# CopterControl_Mag_Pressure.net
KiCad netlist of a schematic drawn in Altium Designer
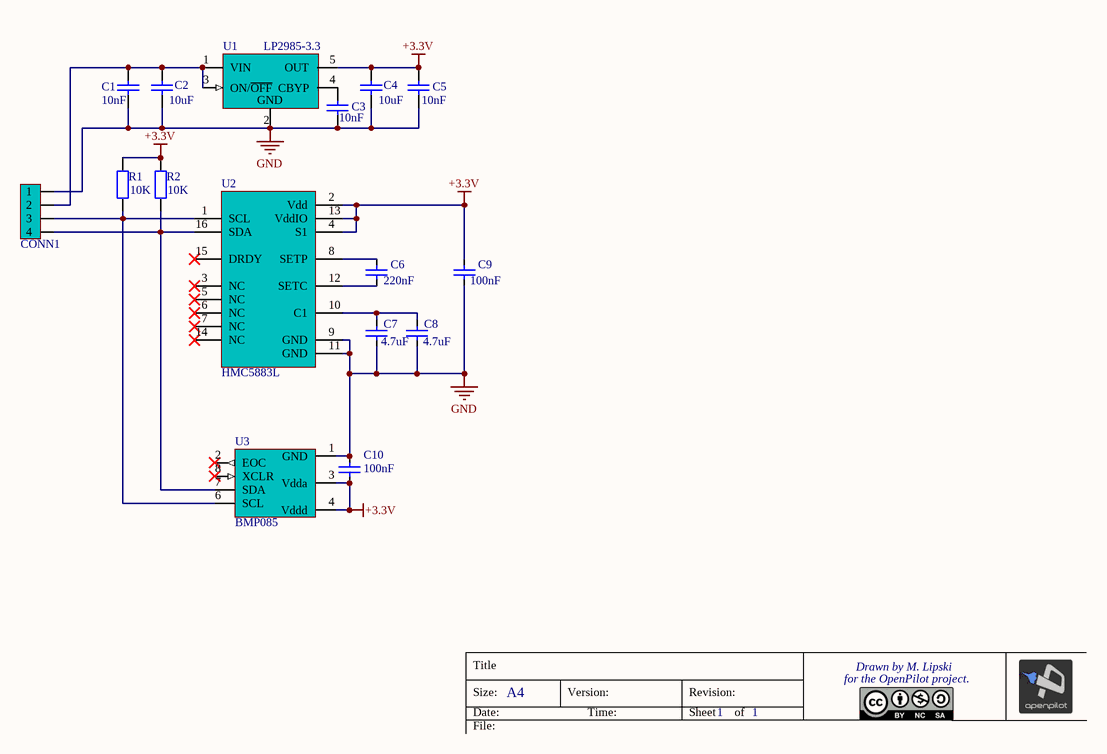
[diagram p0: CopterControl Mag & Pressure.SchDoc]

(export (version "E")
  (design (tool "Eeschema 10.0.6"))
  (components
    (comp (ref "C1")
      (value "10nF")
      (footprint "CAP603L")
      (description "Capacitor SMD")
      (fields (field (name "Comment") "Cap603") (field (name "PUBLISHER") "The OpenPilot Project"))
      (libsource (lib "OpenPilot") (part "Cap603"))
    )
    (comp (ref "C2")
      (value "10uF")
      (footprint "CAP805L")
      (description "Capacitor SMD")
      (fields (field (name "Comment") "Cap805") (field (name "PUBLISHER") "The OpenPilot Project"))
      (libsource (lib "OpenPilot") (part "Cap805"))
    )
    (comp (ref "C3")
      (value "10nF")
      (footprint "CAP603L")
      (description "Capacitor SMD")
      (fields (field (name "Comment") "Cap603") (field (name "PUBLISHER") "The OpenPilot Project"))
      (libsource (lib "OpenPilot") (part "Cap603"))
    )
    (comp (ref "C4")
      (value "10uF")
      (footprint "CAP805L")
      (description "Capacitor SMD")
      (fields (field (name "Comment") "Cap805") (field (name "PUBLISHER") "The OpenPilot Project"))
      (libsource (lib "OpenPilot") (part "Cap805"))
    )
    (comp (ref "C5")
      (value "10nF")
      (footprint "CAP603L")
      (description "Capacitor SMD")
      (fields (field (name "Comment") "Cap603") (field (name "PUBLISHER") "The OpenPilot Project"))
      (libsource (lib "OpenPilot") (part "Cap603"))
    )
    (comp (ref "C6")
      (value "220nF")
      (footprint "CAP603L")
      (description "Capacitor SMD")
      (fields (field (name "Comment") "Cap603") (field (name "PUBLISHER") "The OpenPilot Project"))
      (libsource (lib "") (part "Cap603_1"))
    )
    (comp (ref "C7")
      (value "4.7uF")
      (footprint "CAP603L")
      (description "Capacitor SMD")
      (fields (field (name "Comment") "Cap603") (field (name "PUBLISHER") "The OpenPilot Project"))
      (libsource (lib "") (part "Cap603_1"))
    )
    (comp (ref "C8")
      (value "4.7uF")
      (footprint "CAP603L")
      (description "Capacitor SMD")
      (fields (field (name "Comment") "Cap603") (field (name "PUBLISHER") "The OpenPilot Project"))
      (libsource (lib "") (part "Cap603_1"))
    )
    (comp (ref "C9")
      (value "100nF")
      (footprint "CAP603L")
      (description "Capacitor SMD")
      (fields (field (name "Comment") "Cap603") (field (name "PUBLISHER") "The OpenPilot Project"))
      (libsource (lib "") (part "Cap603_1"))
    )
    (comp (ref "C10")
      (value "100nF")
      (footprint "CAP603L")
      (description "Capacitor SMD")
      (fields (field (name "Comment") "Cap603") (field (name "PUBLISHER") "The OpenPilot Project"))
      (libsource (lib "") (part "Cap603_1"))
    )
    (comp (ref "CONN1")
      (value "JST-SH 4-pin Side Entry Socket")
      (footprint "JST SH 4 Pin Side Entry")
      (fields
        (field (name "MANUFACTURER") "Generic Components")
        (field (name "PUBLISHER") "The OpenPilot Project")
      )
      (libsource (lib "OpenPilot") (part "JST-SH 4-pin Side Entry Socket"))
    )
    (comp (ref "R1")
      (value "10K")
      (footprint "RES603N")
      (description "Resistor SMD")
      (fields (field (name "Comment") "Res603") (field (name "PUBLISHER") "The OpenPilot Project"))
      (libsource (lib "OpenPilot") (part "Res603"))
    )
    (comp (ref "R2")
      (value "10K")
      (footprint "RES603N")
      (description "Resistor SMD")
      (fields (field (name "Comment") "Res603") (field (name "PUBLISHER") "The OpenPilot Project"))
      (libsource (lib "OpenPilot") (part "Res603"))
    )
    (comp (ref "U1")
      (value "LP2985-3.3")
      (footprint "SOT23-5L")
      (description "3.3V 150mA LDO Regulator")
      (libsource (lib "OpenPilot") (part "LP2985-3.3"))
    )
    (comp (ref "U2")
      (value "HMC5883L")
      (footprint "LPCC-16")
      (description "IC, Magnetometer, 3 axis, +/- 8 Oe, I2C, 160Hz")
      (fields (field (name "MANUFACTURER") "Honeywell") (field (name "PUBLISHER") "The OpenPilot Project"))
      (libsource (lib "OpenPilot") (part "HMC5883L"))
    )
    (comp (ref "U3")
      (value "BMP085")
      (footprint "BMP085")
      (description "Barometric Pressure Sensor")
      (libsource (lib "OpenPilot") (part "BMP085"))
    )
  )
  (nets
    (net (code "1") (name "+3.3V") (class "Default")
      (node (ref "C10") (pin "1") (pinfunction "1_1") (pintype "passive"))
      (node (ref "C4") (pin "1") (pinfunction "1_1") (pintype "passive"))
      (node (ref "C5") (pin "1") (pinfunction "1_1") (pintype "passive"))
      (node (ref "C9") (pin "1") (pinfunction "1_1") (pintype "passive"))
      (node (ref "R1") (pin "2") (pinfunction "2_2") (pintype "passive"))
      (node (ref "R2") (pin "2") (pinfunction "2_2") (pintype "passive"))
      (node (ref "U1") (pin "5") (pinfunction "OUT_5") (pintype "power_in"))
      (node (ref "U2") (pin "13") (pinfunction "VddIO_13") (pintype "passive"))
      (node (ref "U2") (pin "2") (pinfunction "Vdd_2") (pintype "power_in"))
      (node (ref "U2") (pin "4") (pinfunction "S1_4") (pintype "passive"))
      (node (ref "U3") (pin "3") (pinfunction "Vdda_3") (pintype "power_in"))
      (node (ref "U3") (pin "4") (pinfunction "Vddd_4") (pintype "power_in"))
    )
    (net (code "2") (name "GND") (class "Default")
      (node (ref "C1") (pin "2") (pinfunction "2_2") (pintype "passive"))
      (node (ref "C10") (pin "2") (pinfunction "2_2") (pintype "passive"))
      (node (ref "C2") (pin "2") (pinfunction "2_2") (pintype "passive"))
      (node (ref "C3") (pin "2") (pinfunction "2_2") (pintype "passive"))
      (node (ref "C4") (pin "2") (pinfunction "2_2") (pintype "passive"))
      (node (ref "C5") (pin "2") (pinfunction "2_2") (pintype "passive"))
      (node (ref "C7") (pin "2") (pinfunction "2_2") (pintype "passive"))
      (node (ref "C8") (pin "2") (pinfunction "2_2") (pintype "passive"))
      (node (ref "C9") (pin "2") (pinfunction "2_2") (pintype "passive"))
      (node (ref "CONN1") (pin "1") (pinfunction "1_1") (pintype "passive"))
      (node (ref "U1") (pin "2") (pinfunction "GND_2") (pintype "power_in"))
      (node (ref "U2") (pin "11") (pinfunction "GND_11") (pintype "passive"))
      (node (ref "U2") (pin "9") (pinfunction "GND_9") (pintype "passive"))
      (node (ref "U3") (pin "1") (pinfunction "GND_1") (pintype "power_in"))
    )
    (net (code "3") (name "Net-(U1-CBYP)") (class "Default")
      (node (ref "C3") (pin "1") (pinfunction "1_1") (pintype "passive"))
      (node (ref "U1") (pin "4") (pinfunction "CBYP_4") (pintype "passive"))
    )
    (net (code "4") (name "Net-(U1-ON{slash}~{OFF})") (class "Default")
      (node (ref "C1") (pin "1") (pinfunction "1_1") (pintype "passive"))
      (node (ref "C2") (pin "1") (pinfunction "1_1") (pintype "passive"))
      (node (ref "CONN1") (pin "2") (pinfunction "2_2") (pintype "passive"))
      (node (ref "U1") (pin "1") (pinfunction "VIN_1") (pintype "power_in"))
      (node (ref "U1") (pin "3") (pinfunction "ON/~{OFF}_3") (pintype "input"))
    )
    (net (code "5") (name "Net-(U2-C1)") (class "Default")
      (node (ref "C7") (pin "1") (pinfunction "1_1") (pintype "passive"))
      (node (ref "C8") (pin "1") (pinfunction "1_1") (pintype "passive"))
      (node (ref "U2") (pin "10") (pinfunction "C1_10") (pintype "passive"))
    )
    (net (code "6") (name "Net-(U2-SCL)") (class "Default")
      (node (ref "CONN1") (pin "3") (pinfunction "3_3") (pintype "passive"))
      (node (ref "R1") (pin "1") (pinfunction "1_1") (pintype "passive"))
      (node (ref "U2") (pin "1") (pinfunction "SCL_1") (pintype "passive"))
      (node (ref "U3") (pin "6") (pinfunction "SCL_6") (pintype "passive"))
    )
    (net (code "7") (name "Net-(U2-SDA)") (class "Default")
      (node (ref "CONN1") (pin "4") (pinfunction "4_4") (pintype "passive"))
      (node (ref "R2") (pin "1") (pinfunction "1_1") (pintype "passive"))
      (node (ref "U2") (pin "16") (pinfunction "SDA_16") (pintype "passive"))
      (node (ref "U3") (pin "7") (pinfunction "SDA_7") (pintype "passive"))
    )
    (net (code "8") (name "Net-(U2-SETC)") (class "Default")
      (node (ref "C6") (pin "1") (pinfunction "1_1") (pintype "passive"))
      (node (ref "U2") (pin "12") (pinfunction "SETC_12") (pintype "power_in"))
    )
    (net (code "9") (name "Net-(U2-SETP)") (class "Default")
      (node (ref "C6") (pin "2") (pinfunction "2_2") (pintype "passive"))
      (node (ref "U2") (pin "8") (pinfunction "SETP_8") (pintype "passive"))
    )
    (net (code "10") (name "unconnected-(U2-DRDY-Pad15)") (class "Default")
      (node (ref "U2") (pin "15") (pinfunction "DRDY_15") (pintype "power_in+no_connect"))
    )
    (net (code "11") (name "unconnected-(U2-NC-Pad3)") (class "Default")
      (node (ref "U2") (pin "3") (pinfunction "NC_3") (pintype "passive+no_connect"))
    )
    (net (code "12") (name "unconnected-(U2-NC-Pad5)") (class "Default")
      (node (ref "U2") (pin "5") (pinfunction "NC_5") (pintype "passive+no_connect"))
    )
    (net (code "13") (name "unconnected-(U2-NC-Pad6)") (class "Default")
      (node (ref "U2") (pin "6") (pinfunction "NC_6") (pintype "passive+no_connect"))
    )
    (net (code "14") (name "unconnected-(U2-NC-Pad7)") (class "Default")
      (node (ref "U2") (pin "7") (pinfunction "NC_7") (pintype "passive+no_connect"))
    )
    (net (code "15") (name "unconnected-(U2-NC-Pad8)") (class "Default")
      (node (ref "U2") (pin "8") (pinfunction "NC_8") (pintype "passive"))
    )
    (net (code "16") (name "unconnected-(U2-NC-Pad14)") (class "Default")
      (node (ref "U2") (pin "14") (pinfunction "NC_14") (pintype "passive+no_connect"))
    )
    (net (code "17") (name "unconnected-(U3-EOC-Pad2)") (class "Default")
      (node (ref "U3") (pin "2") (pinfunction "EOC_2") (pintype "output+no_connect"))
    )
    (net (code "18") (name "unconnected-(U3-NC-Pad5)") (class "Default")
      (node (ref "U3") (pin "5") (pinfunction "NC_5") (pintype "tri_state"))
    )
    (net (code "19") (name "unconnected-(U3-XCLR-Pad8)") (class "Default")
      (node (ref "U3") (pin "8") (pinfunction "XCLR_8") (pintype "input+no_connect"))
    )
  )
)
